# HighCurrentDriver.net
KiCad netlist of a schematic drawn in Altium Designer
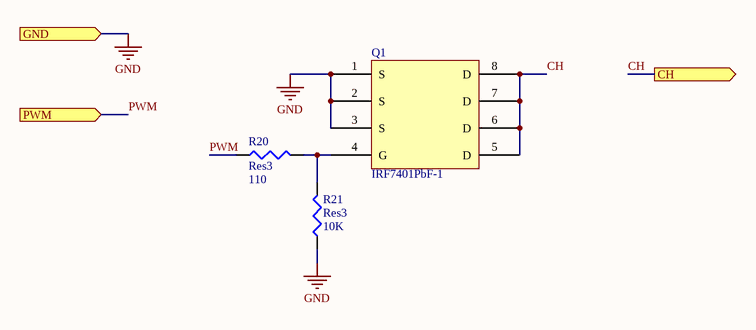
[diagram p0: HighCurrentDriver.SchDoc]

(export (version "E")
  (design (tool "Eeschema 10.0.6"))
  (components
    (comp (ref "Q1")
      (value "IRF7401PbF-1")
      (footprint "SOIC8")
      (description "MOSFET N Channel 20V 8.7A 700mV @ 250uA 22mΩ @ 4.1A,4.5V SOIC-8_150mil RoHS")
      (fields
        (field (name "MANUFACTURER") "Infineon Technologies")
        (field (name "MANUFACTURER PART NUMBER") "IRF7401TRPBF")
      )
      (libsource (lib "IoWLabs") (part "IRF7401"))
    )
    (comp (ref "R20")
      (value "Res3")
      (footprint "J1-0603")
      (description "Resistor")
      (fields
        (field (name "ALTIUM_VALUE") "110")
        (field (name "MANUFACTURER") "ROHM Semicon")
        (field (name "MANUFACTURER PART NUMBER") "MCR03EZPFX1100")
        (field (name "PUBLISHER") "Altium Limited")
      )
      (libsource (lib "Miscellaneous Devices") (part "Res3"))
    )
    (comp (ref "R21")
      (value "Res3")
      (footprint "J1-0603")
      (description "Resistor")
      (fields
        (field (name "ALTIUM_VALUE") "10K")
        (field (name "MANUFACTURER") "PANASONIC")
        (field (name "MANUFACTURER PART NUMBER") "ERJPA3F1002V")
        (field (name "PUBLISHER") "Altium Limited")
      )
      (libsource (lib "Miscellaneous Devices") (part "Res3"))
    )
  )
  (nets
    (net (code "1") (name "/CH") (class "Default")
      (node (ref "Q1") (pin "5") (pinfunction "D_5") (pintype "passive"))
      (node (ref "Q1") (pin "6") (pinfunction "D_6") (pintype "passive"))
      (node (ref "Q1") (pin "7") (pinfunction "D_7") (pintype "passive"))
      (node (ref "Q1") (pin "8") (pinfunction "D_8") (pintype "passive"))
    )
    (net (code "2") (name "/PWM") (class "Default")
      (node (ref "R20") (pin "1") (pinfunction "1_1") (pintype "passive"))
    )
    (net (code "3") (name "GND") (class "Default")
      (node (ref "Q1") (pin "1") (pinfunction "S_1") (pintype "passive"))
      (node (ref "Q1") (pin "2") (pinfunction "S_2") (pintype "passive"))
      (node (ref "Q1") (pin "3") (pinfunction "S_3") (pintype "passive"))
      (node (ref "R21") (pin "1") (pinfunction "1_1") (pintype "passive"))
    )
    (net (code "4") (name "Net-(Q1-G)") (class "Default")
      (node (ref "Q1") (pin "4") (pinfunction "G_4") (pintype "passive"))
      (node (ref "R20") (pin "2") (pinfunction "2_2") (pintype "passive"))
      (node (ref "R21") (pin "2") (pinfunction "2_2") (pintype "passive"))
    )
  )
)
